# MCU.net
KiCad netlist of a schematic drawn in EAGLE
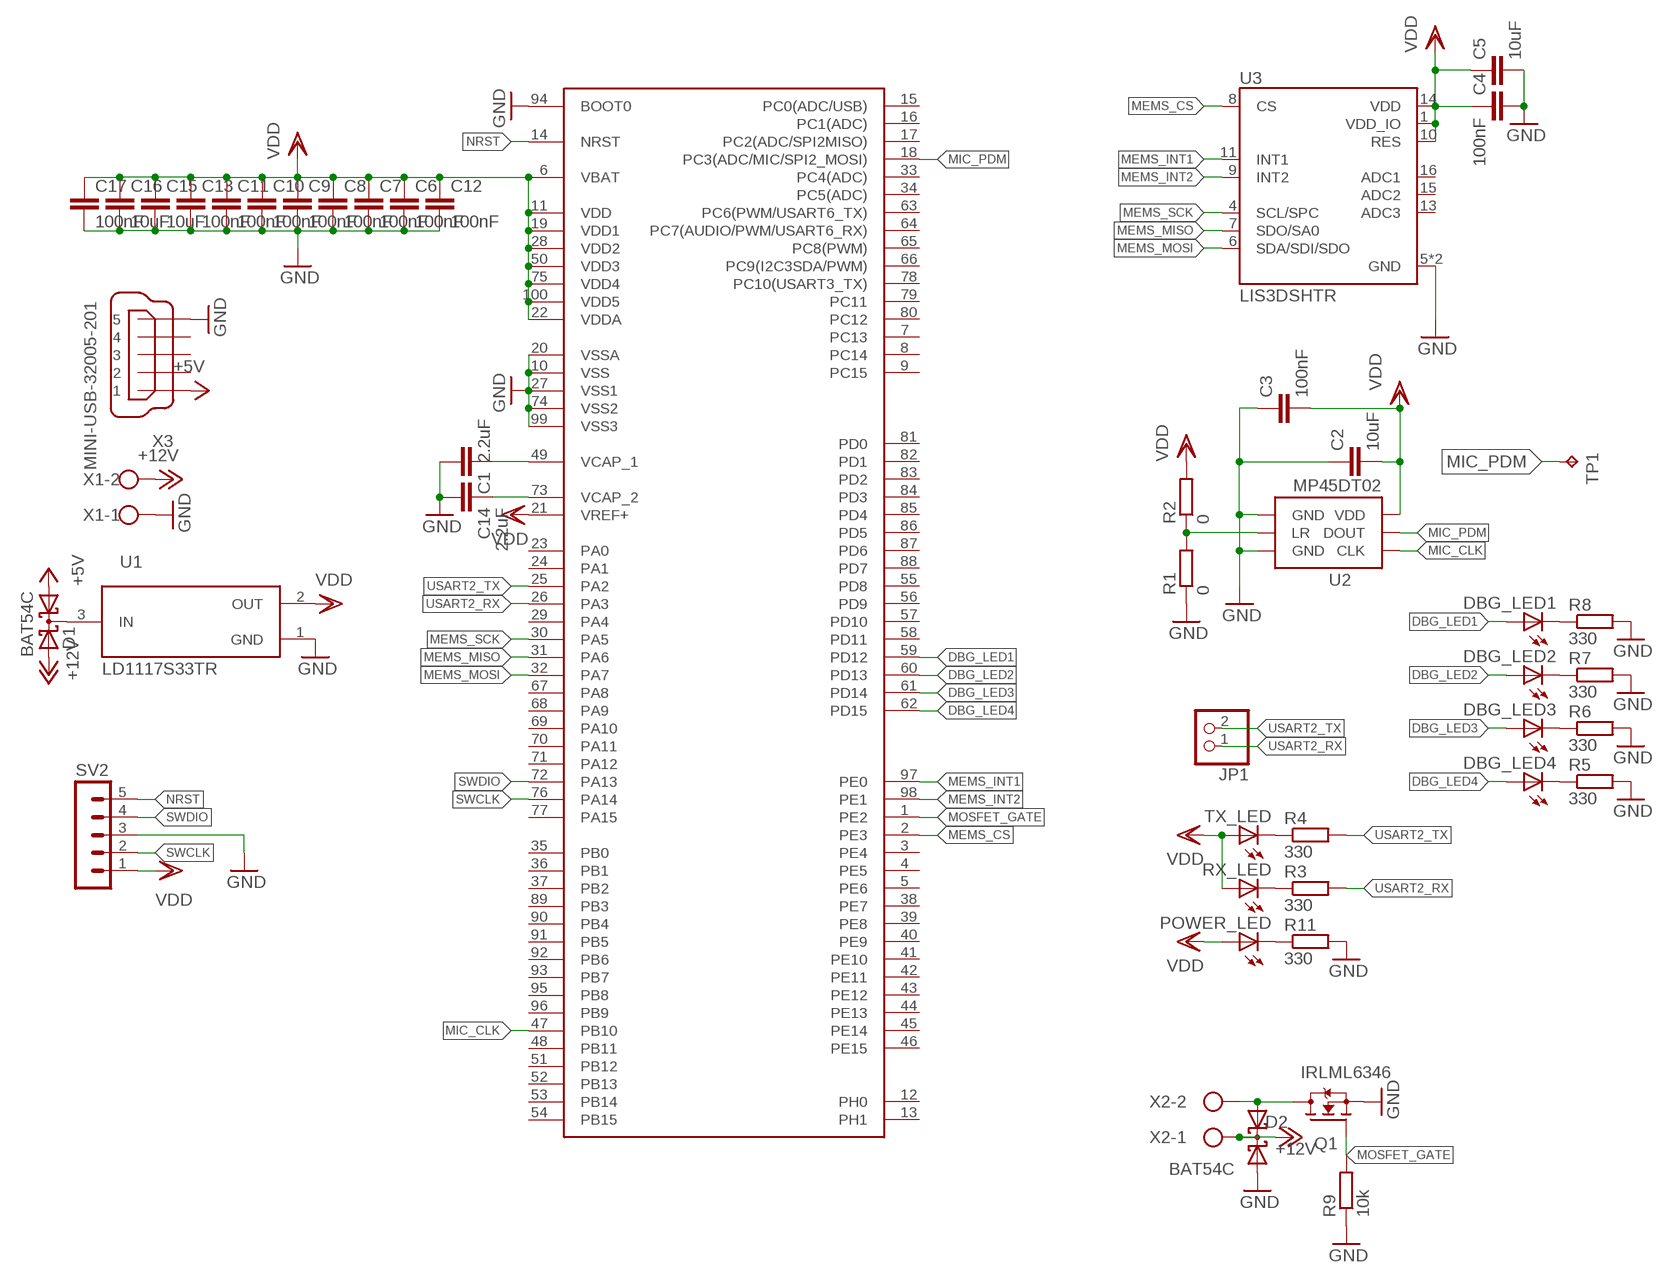
[diagram p0: schematic, sheet 1]

(export (version "E")
  (design (tool "Eeschema 10.0.6"))
  (components
    (comp (ref "C1")
      (value "2.2uF")
      (footprint "eagle-import:C0603")
      (libsource (lib "eagle-import") (part "C-EUC0603"))
    )
    (comp (ref "C2")
      (value "10uF")
      (footprint "eagle-import:C0805")
      (libsource (lib "eagle-import") (part "C-EUC0805"))
    )
    (comp (ref "C3")
      (value "100nF")
      (footprint "eagle-import:C0603")
      (libsource (lib "eagle-import") (part "C-EUC0603"))
    )
    (comp (ref "C4")
      (value "100nF")
      (footprint "eagle-import:C0603")
      (libsource (lib "eagle-import") (part "C-EUC0603"))
    )
    (comp (ref "C5")
      (value "10uF")
      (footprint "eagle-import:C0805")
      (libsource (lib "eagle-import") (part "C-EUC0805"))
    )
    (comp (ref "C6")
      (value "100nF")
      (footprint "eagle-import:C0603")
      (libsource (lib "eagle-import") (part "C-EUC0603"))
    )
    (comp (ref "C7")
      (value "100nF")
      (footprint "eagle-import:C0603")
      (libsource (lib "eagle-import") (part "C-EUC0603"))
    )
    (comp (ref "C8")
      (value "100nF")
      (footprint "eagle-import:C0603")
      (libsource (lib "eagle-import") (part "C-EUC0603"))
    )
    (comp (ref "C9")
      (value "100nF")
      (footprint "eagle-import:C0603")
      (libsource (lib "eagle-import") (part "C-EUC0603"))
    )
    (comp (ref "C10")
      (value "100nF")
      (footprint "eagle-import:C0603")
      (libsource (lib "eagle-import") (part "C-EUC0603"))
    )
    (comp (ref "C11")
      (value "100nF")
      (footprint "eagle-import:C0603")
      (libsource (lib "eagle-import") (part "C-EUC0603"))
    )
    (comp (ref "C12")
      (value "100nF")
      (footprint "eagle-import:C0603")
      (libsource (lib "eagle-import") (part "C-EUC0603"))
    )
    (comp (ref "C13")
      (value "100nF")
      (footprint "eagle-import:C0603")
      (libsource (lib "eagle-import") (part "C-EUC0603"))
    )
    (comp (ref "C14")
      (value "2.2uF")
      (footprint "eagle-import:C0603")
      (libsource (lib "eagle-import") (part "C-EUC0603"))
    )
    (comp (ref "C15")
      (value "10uF")
      (footprint "eagle-import:C0805")
      (libsource (lib "eagle-import") (part "C-EUC0805"))
    )
    (comp (ref "C16")
      (value "10uF")
      (footprint "eagle-import:C0805")
      (libsource (lib "eagle-import") (part "C-EUC0805"))
    )
    (comp (ref "C17")
      (value "100nF")
      (footprint "eagle-import:C0603")
      (libsource (lib "eagle-import") (part "C-EUC0603"))
    )
    (comp (ref "D1")
      (value "BAT54C")
      (footprint "eagle-import:SOT23")
      (libsource (lib "eagle-import") (part "BAT54C"))
    )
    (comp (ref "D2")
      (value "BAT54C")
      (footprint "eagle-import:SOT23")
      (libsource (lib "eagle-import") (part "BAT54C"))
    )
    (comp (ref "DBG_LED1")
      (value "LEDCHIP-LED0603")
      (footprint "eagle-import:CHIP-LED0603")
      (libsource (lib "eagle-import") (part "LEDCHIP-LED0603"))
    )
    (comp (ref "DBG_LED2")
      (value "LEDCHIP-LED0603")
      (footprint "eagle-import:CHIP-LED0603")
      (libsource (lib "eagle-import") (part "LEDCHIP-LED0603"))
    )
    (comp (ref "DBG_LED3")
      (value "LEDCHIP-LED0603")
      (footprint "eagle-import:CHIP-LED0603")
      (libsource (lib "eagle-import") (part "LEDCHIP-LED0603"))
    )
    (comp (ref "DBG_LED4")
      (value "LEDCHIP-LED0603")
      (footprint "eagle-import:CHIP-LED0603")
      (libsource (lib "eagle-import") (part "LEDCHIP-LED0603"))
    )
    (comp (ref "JP1")
      (value "PINHD-1X2")
      (footprint "eagle-import:1X02")
      (libsource (lib "eagle-import") (part "PINHD-1X2"))
    )
    (comp (ref "POWER_LED")
      (value "LEDCHIP-LED0603")
      (footprint "eagle-import:CHIP-LED0603")
      (libsource (lib "eagle-import") (part "LEDCHIP-LED0603"))
    )
    (comp (ref "Q1")
      (value "IRLML6346")
      (footprint "eagle-import:SOT23")
      (fields (field (name "MF") "Fairchild") (field (name "MPN") "BSS138"))
      (libsource (lib "eagle-import") (part "IRLML6346"))
    )
    (comp (ref "R1")
      (value "0")
      (footprint "eagle-import:R0603")
      (libsource (lib "eagle-import") (part "R-EU_R0603"))
    )
    (comp (ref "R2")
      (value "0")
      (footprint "eagle-import:R0603")
      (libsource (lib "eagle-import") (part "R-EU_R0603"))
    )
    (comp (ref "R3")
      (value "330")
      (footprint "eagle-import:R0603")
      (libsource (lib "eagle-import") (part "R-EU_R0603"))
    )
    (comp (ref "R4")
      (value "330")
      (footprint "eagle-import:R0603")
      (libsource (lib "eagle-import") (part "R-EU_R0603"))
    )
    (comp (ref "R5")
      (value "330")
      (footprint "eagle-import:R0603")
      (libsource (lib "eagle-import") (part "R-EU_R0603"))
    )
    (comp (ref "R6")
      (value "330")
      (footprint "eagle-import:R0603")
      (libsource (lib "eagle-import") (part "R-EU_R0603"))
    )
    (comp (ref "R7")
      (value "330")
      (footprint "eagle-import:R0603")
      (libsource (lib "eagle-import") (part "R-EU_R0603"))
    )
    (comp (ref "R8")
      (value "330")
      (footprint "eagle-import:R0603")
      (libsource (lib "eagle-import") (part "R-EU_R0603"))
    )
    (comp (ref "R9")
      (value "10k")
      (footprint "eagle-import:R0603")
      (libsource (lib "eagle-import") (part "R-EU_R0603"))
    )
    (comp (ref "R11")
      (value "330")
      (footprint "eagle-import:R0603")
      (libsource (lib "eagle-import") (part "R-EU_R0603"))
    )
    (comp (ref "RX_LED")
      (value "LEDCHIP-LED0603")
      (footprint "eagle-import:CHIP-LED0603")
      (libsource (lib "eagle-import") (part "LEDCHIP-LED0603"))
    )
    (comp (ref "SV2")
      (value "MA05-1")
      (footprint "eagle-import:MA05-1")
      (libsource (lib "eagle-import") (part "MA05-1"))
    )
    (comp (ref "TP1")
      (value "TPB1,27")
      (footprint "eagle-import:B1,27")
      (libsource (lib "eagle-import") (part "TPB1,27"))
    )
    (comp (ref "TX_LED")
      (value "LEDCHIP-LED0603")
      (footprint "eagle-import:CHIP-LED0603")
      (libsource (lib "eagle-import") (part "LEDCHIP-LED0603"))
    )
    (comp (ref "U$1")
      (value "STM32F407STM32D40X")
      (footprint "eagle-import:LQFP100")
      (libsource (lib "eagle-import") (part "STM32F407STM32D40X"))
    )
    (comp (ref "U1")
      (value "LD1117S33TR")
      (footprint "eagle-import:SOT230P700X180-4N")
      (fields (field (name "MF") "STMicroelectronics"))
      (libsource (lib "eagle-import") (part "LD1117S33TR"))
    )
    (comp (ref "U2")
      (value "MP45DT02")
      (footprint "eagle-import:ST_HLGA6")
      (fields (field (name "MF") "STMicroelectronics"))
      (libsource (lib "eagle-import") (part "MP45DT02"))
    )
    (comp (ref "U3")
      (value "LIS3DSHTR")
      (footprint "eagle-import:LGA16R50P5X3_300X300X100N")
      (fields (field (name "MF") "STMicroelectronics"))
      (libsource (lib "eagle-import") (part "LIS3DSHTR"))
    )
    (comp (ref "X1")
      (value "W237-102")
      (footprint "eagle-import:W237-102")
      (fields (field (name "MPN") "237-102"))
      (libsource (lib "eagle-import") (part "W237-102"))
    )
    (comp (ref "X2")
      (value "W237-102")
      (footprint "eagle-import:W237-102")
      (fields (field (name "MPN") "237-102"))
      (libsource (lib "eagle-import") (part "W237-102"))
    )
    (comp (ref "X3")
      (value "MINI-USB-32005-201")
      (footprint "eagle-import:32005-201")
      (libsource (lib "eagle-import") (part "MINI-USB-32005-201"))
    )
  )
  (nets
    (net (code "1") (name "+5V") (class "Default")
      (node (ref "D1") (pin "1") (pinfunction "A1_1") (pintype "passive"))
      (node (ref "X3") (pin "1") (pinfunction "1_1") (pintype "passive"))
    )
    (net (code "2") (name "+12V") (class "Default")
      (node (ref "D1") (pin "2") (pinfunction "A2_2") (pintype "passive"))
      (node (ref "D2") (pin "3") (pinfunction "CC_3") (pintype "passive"))
      (node (ref "X1") (pin "2") (pinfunction "KL_2") (pintype "passive"))
      (node (ref "X2") (pin "1") (pinfunction "KL_1") (pintype "passive"))
    )
    (net (code "3") (name "DBG_LED1") (class "Default")
      (node (ref "DBG_LED1") (pin "A") (pinfunction "A_A") (pintype "passive"))
      (node (ref "U$1") (pin "59") (pinfunction "PD12_59") (pintype "bidirectional"))
    )
    (net (code "4") (name "DBG_LED2") (class "Default")
      (node (ref "DBG_LED2") (pin "A") (pinfunction "A_A") (pintype "passive"))
      (node (ref "U$1") (pin "60") (pinfunction "PD13_60") (pintype "bidirectional"))
    )
    (net (code "5") (name "DBG_LED3") (class "Default")
      (node (ref "DBG_LED3") (pin "A") (pinfunction "A_A") (pintype "passive"))
      (node (ref "U$1") (pin "61") (pinfunction "PD14_61") (pintype "bidirectional"))
    )
    (net (code "6") (name "DBG_LED4") (class "Default")
      (node (ref "DBG_LED4") (pin "A") (pinfunction "A_A") (pintype "passive"))
      (node (ref "U$1") (pin "62") (pinfunction "PD15_62") (pintype "bidirectional"))
    )
    (net (code "7") (name "GND") (class "Default")
      (node (ref "C1") (pin "2") (pinfunction "2_2") (pintype "passive"))
      (node (ref "C10") (pin "2") (pinfunction "2_2") (pintype "passive"))
      (node (ref "C11") (pin "2") (pinfunction "2_2") (pintype "passive"))
      (node (ref "C12") (pin "2") (pinfunction "2_2") (pintype "passive"))
      (node (ref "C13") (pin "2") (pinfunction "2_2") (pintype "passive"))
      (node (ref "C14") (pin "2") (pinfunction "2_2") (pintype "passive"))
      (node (ref "C15") (pin "2") (pinfunction "2_2") (pintype "passive"))
      (node (ref "C16") (pin "2") (pinfunction "2_2") (pintype "passive"))
      (node (ref "C17") (pin "2") (pinfunction "2_2") (pintype "passive"))
      (node (ref "C2") (pin "1") (pinfunction "1_1") (pintype "passive"))
      (node (ref "C3") (pin "1") (pinfunction "1_1") (pintype "passive"))
      (node (ref "C4") (pin "2") (pinfunction "2_2") (pintype "passive"))
      (node (ref "C5") (pin "2") (pinfunction "2_2") (pintype "passive"))
      (node (ref "C6") (pin "2") (pinfunction "2_2") (pintype "passive"))
      (node (ref "C7") (pin "2") (pinfunction "2_2") (pintype "passive"))
      (node (ref "C8") (pin "2") (pinfunction "2_2") (pintype "passive"))
      (node (ref "C9") (pin "2") (pinfunction "2_2") (pintype "passive"))
      (node (ref "D2") (pin "1") (pinfunction "A1_1") (pintype "passive"))
      (node (ref "Q1") (pin "2") (pinfunction "S_2") (pintype "passive"))
      (node (ref "R1") (pin "1") (pinfunction "1_1") (pintype "passive"))
      (node (ref "R11") (pin "2") (pinfunction "2_2") (pintype "passive"))
      (node (ref "R5") (pin "2") (pinfunction "2_2") (pintype "passive"))
      (node (ref "R6") (pin "2") (pinfunction "2_2") (pintype "passive"))
      (node (ref "R7") (pin "2") (pinfunction "2_2") (pintype "passive"))
      (node (ref "R8") (pin "2") (pinfunction "2_2") (pintype "passive"))
      (node (ref "R9") (pin "1") (pinfunction "1_1") (pintype "passive"))
      (node (ref "SV2") (pin "3") (pinfunction "3_3") (pintype "passive"))
      (node (ref "U$1") (pin "10") (pinfunction "VSS_10") (pintype "bidirectional"))
      (node (ref "U$1") (pin "20") (pinfunction "VSSA_20") (pintype "bidirectional"))
      (node (ref "U$1") (pin "27") (pinfunction "VSS1_27") (pintype "bidirectional"))
      (node (ref "U$1") (pin "74") (pinfunction "VSS2_74") (pintype "bidirectional"))
      (node (ref "U$1") (pin "94") (pinfunction "BOOT0_94") (pintype "bidirectional"))
      (node (ref "U$1") (pin "99") (pinfunction "VSS3_99") (pintype "bidirectional"))
      (node (ref "U1") (pin "1") (pinfunction "GND_1") (pintype "power_in"))
      (node (ref "U2") (pin "1") (pinfunction "GND_1") (pintype "bidirectional"))
      (node (ref "U2") (pin "3") (pinfunction "GND_3") (pintype "bidirectional"))
      (node (ref "U3") (pin "12") (pinfunction "GND_12") (pintype "power_in"))
      (node (ref "U3") (pin "5") (pinfunction "GND_5") (pintype "power_in"))
      (node (ref "X1") (pin "1") (pinfunction "KL_1") (pintype "passive"))
      (node (ref "X3") (pin "5") (pinfunction "5_5") (pintype "passive"))
    )
    (net (code "8") (name "MEMS_CS") (class "Default")
      (node (ref "U$1") (pin "2") (pinfunction "PE3_2") (pintype "bidirectional"))
      (node (ref "U3") (pin "8") (pinfunction "CS_8") (pintype "input"))
    )
    (net (code "9") (name "MEMS_INT1") (class "Default")
      (node (ref "U$1") (pin "97") (pinfunction "PE0_97") (pintype "bidirectional"))
      (node (ref "U3") (pin "11") (pinfunction "INT1_11") (pintype "input"))
    )
    (net (code "10") (name "MEMS_INT2") (class "Default")
      (node (ref "U$1") (pin "98") (pinfunction "PE1_98") (pintype "bidirectional"))
      (node (ref "U3") (pin "9") (pinfunction "INT2_9") (pintype "input"))
    )
    (net (code "11") (name "MEMS_MISO") (class "Default")
      (node (ref "U$1") (pin "31") (pinfunction "PA6_31") (pintype "bidirectional"))
      (node (ref "U3") (pin "7") (pinfunction "SDO/SA0_7") (pintype "output"))
    )
    (net (code "12") (name "MEMS_MOSI") (class "Default")
      (node (ref "U$1") (pin "32") (pinfunction "PA7_32") (pintype "bidirectional"))
      (node (ref "U3") (pin "6") (pinfunction "SDA/SDI/SDO_6") (pintype "bidirectional"))
    )
    (net (code "13") (name "MEMS_SCK") (class "Default")
      (node (ref "U$1") (pin "30") (pinfunction "PA5_30") (pintype "bidirectional"))
      (node (ref "U3") (pin "4") (pinfunction "SCL/SPC_4") (pintype "input"))
    )
    (net (code "14") (name "MIC_CLK") (class "Default")
      (node (ref "U$1") (pin "47") (pinfunction "PB10_47") (pintype "bidirectional"))
      (node (ref "U2") (pin "4") (pinfunction "CLK_4") (pintype "bidirectional"))
    )
    (net (code "15") (name "MIC_PDM") (class "Default")
      (node (ref "TP1") (pin "TP") (pinfunction "TP_TP") (pintype "input"))
      (node (ref "U$1") (pin "18") (pinfunction "PC3(ADC/MIC/SPI2_MOSI)_18") (pintype "bidirectional"))
      (node (ref "U2") (pin "5") (pinfunction "DOUT_5") (pintype "bidirectional"))
    )
    (net (code "16") (name "MOSFET_GATE") (class "Default")
      (node (ref "Q1") (pin "1") (pinfunction "G_1") (pintype "passive"))
      (node (ref "R9") (pin "2") (pinfunction "2_2") (pintype "passive"))
      (node (ref "U$1") (pin "1") (pinfunction "PE2_1") (pintype "bidirectional"))
    )
    (net (code "17") (name "NRST") (class "Default")
      (node (ref "SV2") (pin "5") (pinfunction "5_5") (pintype "passive"))
      (node (ref "U$1") (pin "14") (pinfunction "NRST_14") (pintype "bidirectional"))
    )
    (net (code "18") (name "Net-(D1-CC)") (class "Default")
      (node (ref "D1") (pin "3") (pinfunction "CC_3") (pintype "passive"))
      (node (ref "U1") (pin "3") (pinfunction "IN_3") (pintype "input"))
    )
    (net (code "19") (name "Net-(D2-A2)") (class "Default")
      (node (ref "D2") (pin "2") (pinfunction "A2_2") (pintype "passive"))
      (node (ref "Q1") (pin "3") (pinfunction "D_3") (pintype "passive"))
      (node (ref "X2") (pin "2") (pinfunction "KL_2") (pintype "passive"))
    )
    (net (code "20") (name "Net-(DBG_LED1-PadC)") (class "Default")
      (node (ref "DBG_LED1") (pin "C") (pinfunction "C_C") (pintype "passive"))
      (node (ref "R8") (pin "1") (pinfunction "1_1") (pintype "passive"))
    )
    (net (code "21") (name "Net-(DBG_LED2-PadC)") (class "Default")
      (node (ref "DBG_LED2") (pin "C") (pinfunction "C_C") (pintype "passive"))
      (node (ref "R7") (pin "1") (pinfunction "1_1") (pintype "passive"))
    )
    (net (code "22") (name "Net-(DBG_LED3-PadC)") (class "Default")
      (node (ref "DBG_LED3") (pin "C") (pinfunction "C_C") (pintype "passive"))
      (node (ref "R6") (pin "1") (pinfunction "1_1") (pintype "passive"))
    )
    (net (code "23") (name "Net-(DBG_LED4-PadC)") (class "Default")
      (node (ref "DBG_LED4") (pin "C") (pinfunction "C_C") (pintype "passive"))
      (node (ref "R5") (pin "1") (pinfunction "1_1") (pintype "passive"))
    )
    (net (code "24") (name "Net-(POWER_LED-PadC)") (class "Default")
      (node (ref "POWER_LED") (pin "C") (pinfunction "C_C") (pintype "passive"))
      (node (ref "R11") (pin "1") (pinfunction "1_1") (pintype "passive"))
    )
    (net (code "25") (name "Net-(R3-Pad1)") (class "Default")
      (node (ref "R3") (pin "1") (pinfunction "1_1") (pintype "passive"))
      (node (ref "RX_LED") (pin "C") (pinfunction "C_C") (pintype "passive"))
    )
    (net (code "26") (name "Net-(R4-Pad1)") (class "Default")
      (node (ref "R4") (pin "1") (pinfunction "1_1") (pintype "passive"))
      (node (ref "TX_LED") (pin "C") (pinfunction "C_C") (pintype "passive"))
    )
    (net (code "27") (name "Net-(U$1-VCAP_1)") (class "Default")
      (node (ref "C1") (pin "1") (pinfunction "1_1") (pintype "passive"))
      (node (ref "U$1") (pin "49") (pinfunction "VCAP_1_49") (pintype "bidirectional"))
    )
    (net (code "28") (name "Net-(U$1-VCAP_2)") (class "Default")
      (node (ref "C14") (pin "1") (pinfunction "1_1") (pintype "passive"))
      (node (ref "U$1") (pin "73") (pinfunction "VCAP_2_73") (pintype "bidirectional"))
    )
    (net (code "29") (name "Net-(U2-LR)") (class "Default")
      (node (ref "R1") (pin "2") (pinfunction "2_2") (pintype "passive"))
      (node (ref "R2") (pin "1") (pinfunction "1_1") (pintype "passive"))
      (node (ref "U2") (pin "2") (pinfunction "LR_2") (pintype "bidirectional"))
    )
    (net (code "30") (name "SWCLK") (class "Default")
      (node (ref "SV2") (pin "2") (pinfunction "2_2") (pintype "passive"))
      (node (ref "U$1") (pin "76") (pinfunction "PA14_76") (pintype "bidirectional"))
    )
    (net (code "31") (name "SWDIO") (class "Default")
      (node (ref "SV2") (pin "4") (pinfunction "4_4") (pintype "passive"))
      (node (ref "U$1") (pin "72") (pinfunction "PA13_72") (pintype "bidirectional"))
    )
    (net (code "32") (name "USART2_RX") (class "Default")
      (node (ref "JP1") (pin "1") (pinfunction "1_1") (pintype "passive"))
      (node (ref "R3") (pin "2") (pinfunction "2_2") (pintype "passive"))
      (node (ref "U$1") (pin "26") (pinfunction "PA3_26") (pintype "bidirectional"))
    )
    (net (code "33") (name "USART2_TX") (class "Default")
      (node (ref "JP1") (pin "2") (pinfunction "2_2") (pintype "passive"))
      (node (ref "R4") (pin "2") (pinfunction "2_2") (pintype "passive"))
      (node (ref "U$1") (pin "25") (pinfunction "PA2_25") (pintype "bidirectional"))
    )
    (net (code "34") (name "VDD") (class "Default")
      (node (ref "C10") (pin "1") (pinfunction "1_1") (pintype "passive"))
      (node (ref "C11") (pin "1") (pinfunction "1_1") (pintype "passive"))
      (node (ref "C12") (pin "1") (pinfunction "1_1") (pintype "passive"))
      (node (ref "C13") (pin "1") (pinfunction "1_1") (pintype "passive"))
      (node (ref "C15") (pin "1") (pinfunction "1_1") (pintype "passive"))
      (node (ref "C16") (pin "1") (pinfunction "1_1") (pintype "passive"))
      (node (ref "C17") (pin "1") (pinfunction "1_1") (pintype "passive"))
      (node (ref "C2") (pin "2") (pinfunction "2_2") (pintype "passive"))
      (node (ref "C3") (pin "2") (pinfunction "2_2") (pintype "passive"))
      (node (ref "C4") (pin "1") (pinfunction "1_1") (pintype "passive"))
      (node (ref "C5") (pin "1") (pinfunction "1_1") (pintype "passive"))
      (node (ref "C6") (pin "1") (pinfunction "1_1") (pintype "passive"))
      (node (ref "C7") (pin "1") (pinfunction "1_1") (pintype "passive"))
      (node (ref "C8") (pin "1") (pinfunction "1_1") (pintype "passive"))
      (node (ref "C9") (pin "1") (pinfunction "1_1") (pintype "passive"))
      (node (ref "POWER_LED") (pin "A") (pinfunction "A_A") (pintype "passive"))
      (node (ref "R2") (pin "2") (pinfunction "2_2") (pintype "passive"))
      (node (ref "RX_LED") (pin "A") (pinfunction "A_A") (pintype "passive"))
      (node (ref "SV2") (pin "1") (pinfunction "1_1") (pintype "passive"))
      (node (ref "TX_LED") (pin "A") (pinfunction "A_A") (pintype "passive"))
      (node (ref "U$1") (pin "100") (pinfunction "VDD5_100") (pintype "bidirectional"))
      (node (ref "U$1") (pin "11") (pinfunction "VDD_11") (pintype "bidirectional"))
      (node (ref "U$1") (pin "19") (pinfunction "VDD1_19") (pintype "bidirectional"))
      (node (ref "U$1") (pin "21") (pinfunction "VREF+_21") (pintype "bidirectional"))
      (node (ref "U$1") (pin "22") (pinfunction "VDDA_22") (pintype "bidirectional"))
      (node (ref "U$1") (pin "28") (pinfunction "VDD2_28") (pintype "bidirectional"))
      (node (ref "U$1") (pin "50") (pinfunction "VDD3_50") (pintype "bidirectional"))
      (node (ref "U$1") (pin "6") (pinfunction "VBAT_6") (pintype "bidirectional"))
      (node (ref "U$1") (pin "75") (pinfunction "VDD4_75") (pintype "bidirectional"))
      (node (ref "U1") (pin "2") (pinfunction "OUT_2") (pintype "output"))
      (node (ref "U2") (pin "6") (pinfunction "VDD_6") (pintype "bidirectional"))
      (node (ref "U3") (pin "1") (pinfunction "VDD_IO_1") (pintype "power_in"))
      (node (ref "U3") (pin "10") (pinfunction "RES_10") (pintype "power_in"))
      (node (ref "U3") (pin "14") (pinfunction "VDD_14") (pintype "power_in"))
    )
    (net (code "35") (name "unconnected-(U$1-PA0-Pad23)") (class "Default")
      (node (ref "U$1") (pin "23") (pinfunction "PA0_23") (pintype "bidirectional"))
    )
    (net (code "36") (name "unconnected-(U$1-PA1-Pad24)") (class "Default")
      (node (ref "U$1") (pin "24") (pinfunction "PA1_24") (pintype "bidirectional"))
    )
    (net (code "37") (name "unconnected-(U$1-PA4-Pad29)") (class "Default")
      (node (ref "U$1") (pin "29") (pinfunction "PA4_29") (pintype "bidirectional"))
    )
    (net (code "38") (name "unconnected-(U$1-PA8-Pad67)") (class "Default")
      (node (ref "U$1") (pin "67") (pinfunction "PA8_67") (pintype "bidirectional"))
    )
    (net (code "39") (name "unconnected-(U$1-PA9-Pad68)") (class "Default")
      (node (ref "U$1") (pin "68") (pinfunction "PA9_68") (pintype "bidirectional"))
    )
    (net (code "40") (name "unconnected-(U$1-PA10-Pad69)") (class "Default")
      (node (ref "U$1") (pin "69") (pinfunction "PA10_69") (pintype "bidirectional"))
    )
    (net (code "41") (name "unconnected-(U$1-PA11-Pad70)") (class "Default")
      (node (ref "U$1") (pin "70") (pinfunction "PA11_70") (pintype "bidirectional"))
    )
    (net (code "42") (name "unconnected-(U$1-PA12-Pad71)") (class "Default")
      (node (ref "U$1") (pin "71") (pinfunction "PA12_71") (pintype "bidirectional"))
    )
    (net (code "43") (name "unconnected-(U$1-PA15-Pad77)") (class "Default")
      (node (ref "U$1") (pin "77") (pinfunction "PA15_77") (pintype "bidirectional"))
    )
    (net (code "44") (name "unconnected-(U$1-PB0-Pad35)") (class "Default")
      (node (ref "U$1") (pin "35") (pinfunction "PB0_35") (pintype "bidirectional"))
    )
    (net (code "45") (name "unconnected-(U$1-PB1-Pad36)") (class "Default")
      (node (ref "U$1") (pin "36") (pinfunction "PB1_36") (pintype "bidirectional"))
    )
    (net (code "46") (name "unconnected-(U$1-PB2-Pad37)") (class "Default")
      (node (ref "U$1") (pin "37") (pinfunction "PB2_37") (pintype "bidirectional"))
    )
    (net (code "47") (name "unconnected-(U$1-PB3-Pad89)") (class "Default")
      (node (ref "U$1") (pin "89") (pinfunction "PB3_89") (pintype "bidirectional"))
    )
    (net (code "48") (name "unconnected-(U$1-PB4-Pad90)") (class "Default")
      (node (ref "U$1") (pin "90") (pinfunction "PB4_90") (pintype "bidirectional"))
    )
    (net (code "49") (name "unconnected-(U$1-PB5-Pad91)") (class "Default")
      (node (ref "U$1") (pin "91") (pinfunction "PB5_91") (pintype "bidirectional"))
    )
    (net (code "50") (name "unconnected-(U$1-PB6-Pad92)") (class "Default")
      (node (ref "U$1") (pin "92") (pinfunction "PB6_92") (pintype "bidirectional"))
    )
    (net (code "51") (name "unconnected-(U$1-PB7-Pad93)") (class "Default")
      (node (ref "U$1") (pin "93") (pinfunction "PB7_93") (pintype "bidirectional"))
    )
    (net (code "52") (name "unconnected-(U$1-PB8-Pad95)") (class "Default")
      (node (ref "U$1") (pin "95") (pinfunction "PB8_95") (pintype "bidirectional"))
    )
    (net (code "53") (name "unconnected-(U$1-PB9-Pad96)") (class "Default")
      (node (ref "U$1") (pin "96") (pinfunction "PB9_96") (pintype "bidirectional"))
    )
    (net (code "54") (name "unconnected-(U$1-PB11-Pad48)") (class "Default")
      (node (ref "U$1") (pin "48") (pinfunction "PB11_48") (pintype "bidirectional"))
    )
    (net (code "55") (name "unconnected-(U$1-PB12-Pad51)") (class "Default")
      (node (ref "U$1") (pin "51") (pinfunction "PB12_51") (pintype "bidirectional"))
    )
    (net (code "56") (name "unconnected-(U$1-PB13-Pad52)") (class "Default")
      (node (ref "U$1") (pin "52") (pinfunction "PB13_52") (pintype "bidirectional"))
    )
    (net (code "57") (name "unconnected-(U$1-PB14-Pad53)") (class "Default")
      (node (ref "U$1") (pin "53") (pinfunction "PB14_53") (pintype "bidirectional"))
    )
    (net (code "58") (name "unconnected-(U$1-PB15-Pad54)") (class "Default")
      (node (ref "U$1") (pin "54") (pinfunction "PB15_54") (pintype "bidirectional"))
    )
    (net (code "59") (name "unconnected-(U$1-PC0(ADC{slash}USB)-Pad15)") (class "Default")
      (node (ref "U$1") (pin "15") (pinfunction "PC0(ADC/USB)_15") (pintype "bidirectional"))
    )
    (net (code "60") (name "unconnected-(U$1-PC1(ADC)-Pad16)") (class "Default")
      (node (ref "U$1") (pin "16") (pinfunction "PC1(ADC)_16") (pintype "bidirectional"))
    )
    (net (code "61") (name "unconnected-(U$1-PC2(ADC{slash}SPI2MISO)-Pad17)") (class "Default")
      (node (ref "U$1") (pin "17") (pinfunction "PC2(ADC/SPI2MISO)_17") (pintype "bidirectional"))
    )
    (net (code "62") (name "unconnected-(U$1-PC4(ADC)-Pad33)") (class "Default")
      (node (ref "U$1") (pin "33") (pinfunction "PC4(ADC)_33") (pintype "bidirectional"))
    )
    (net (code "63") (name "unconnected-(U$1-PC5(ADC)-Pad34)") (class "Default")
      (node (ref "U$1") (pin "34") (pinfunction "PC5(ADC)_34") (pintype "bidirectional"))
    )
    (net (code "64") (name "unconnected-(U$1-PC6(PWM{slash}USART6_TX)-Pad63)") (class "Default")
      (node (ref "U$1") (pin "63") (pinfunction "PC6(PWM/USART6_TX)_63") (pintype "bidirectional"))
    )
    (net (code "65") (name "unconnected-(U$1-PC7(AUDIO{slash}PWM{slash}USART6_RX)-Pad64)") (class "Default")
      (node (ref "U$1") (pin "64") (pinfunction "PC7(AUDIO/PWM/USART6_RX)_64") (pintype "bidirectional"))
    )
    (net (code "66") (name "unconnected-(U$1-PC8(PWM)-Pad65)") (class "Default")
      (node (ref "U$1") (pin "65") (pinfunction "PC8(PWM)_65") (pintype "bidirectional"))
    )
    (net (code "67") (name "unconnected-(U$1-PC9(I2C3SDA{slash}PWM)-Pad66)") (class "Default")
      (node (ref "U$1") (pin "66") (pinfunction "PC9(I2C3SDA/PWM)_66") (pintype "bidirectional"))
    )
    (net (code "68") (name "unconnected-(U$1-PC10(USART3_TX)-Pad78)") (class "Default")
      (node (ref "U$1") (pin "78") (pinfunction "PC10(USART3_TX)_78") (pintype "bidirectional"))
    )
    (net (code "69") (name "unconnected-(U$1-PC11-Pad79)") (class "Default")
      (node (ref "U$1") (pin "79") (pinfunction "PC11_79") (pintype "bidirectional"))
    )
    (net (code "70") (name "unconnected-(U$1-PC12-Pad80)") (class "Default")
      (node (ref "U$1") (pin "80") (pinfunction "PC12_80") (pintype "bidirectional"))
    )
    (net (code "71") (name "unconnected-(U$1-PC13-Pad7)") (class "Default")
      (node (ref "U$1") (pin "7") (pinfunction "PC13_7") (pintype "bidirectional"))
    )
    (net (code "72") (name "unconnected-(U$1-PC14-Pad8)") (class "Default")
      (node (ref "U$1") (pin "8") (pinfunction "PC14_8") (pintype "bidirectional"))
    )
    (net (code "73") (name "unconnected-(U$1-PC15-Pad9)") (class "Default")
      (node (ref "U$1") (pin "9") (pinfunction "PC15_9") (pintype "bidirectional"))
    )
    (net (code "74") (name "unconnected-(U$1-PD0-Pad81)") (class "Default")
      (node (ref "U$1") (pin "81") (pinfunction "PD0_81") (pintype "bidirectional"))
    )
    (net (code "75") (name "unconnected-(U$1-PD1-Pad82)") (class "Default")
      (node (ref "U$1") (pin "82") (pinfunction "PD1_82") (pintype "bidirectional"))
    )
    (net (code "76") (name "unconnected-(U$1-PD2-Pad83)") (class "Default")
      (node (ref "U$1") (pin "83") (pinfunction "PD2_83") (pintype "bidirectional"))
    )
    (net (code "77") (name "unconnected-(U$1-PD3-Pad84)") (class "Default")
      (node (ref "U$1") (pin "84") (pinfunction "PD3_84") (pintype "bidirectional"))
    )
    (net (code "78") (name "unconnected-(U$1-PD4-Pad85)") (class "Default")
      (node (ref "U$1") (pin "85") (pinfunction "PD4_85") (pintype "bidirectional"))
    )
    (net (code "79") (name "unconnected-(U$1-PD5-Pad86)") (class "Default")
      (node (ref "U$1") (pin "86") (pinfunction "PD5_86") (pintype "bidirectional"))
    )
    (net (code "80") (name "unconnected-(U$1-PD6-Pad87)") (class "Default")
      (node (ref "U$1") (pin "87") (pinfunction "PD6_87") (pintype "bidirectional"))
    )
    (net (code "81") (name "unconnected-(U$1-PD7-Pad88)") (class "Default")
      (node (ref "U$1") (pin "88") (pinfunction "PD7_88") (pintype "bidirectional"))
    )
    (net (code "82") (name "unconnected-(U$1-PD8-Pad55)") (class "Default")
      (node (ref "U$1") (pin "55") (pinfunction "PD8_55") (pintype "bidirectional"))
    )
    (net (code "83") (name "unconnected-(U$1-PD9-Pad56)") (class "Default")
      (node (ref "U$1") (pin "56") (pinfunction "PD9_56") (pintype "bidirectional"))
    )
    (net (code "84") (name "unconnected-(U$1-PD10-Pad57)") (class "Default")
      (node (ref "U$1") (pin "57") (pinfunction "PD10_57") (pintype "bidirectional"))
    )
    (net (code "85") (name "unconnected-(U$1-PD11-Pad58)") (class "Default")
      (node (ref "U$1") (pin "58") (pinfunction "PD11_58") (pintype "bidirectional"))
    )
    (net (code "86") (name "unconnected-(U$1-PE4-Pad3)") (class "Default")
      (node (ref "U$1") (pin "3") (pinfunction "PE4_3") (pintype "bidirectional"))
    )
    (net (code "87") (name "unconnected-(U$1-PE5-Pad4)") (class "Default")
      (node (ref "U$1") (pin "4") (pinfunction "PE5_4") (pintype "bidirectional"))
    )
    (net (code "88") (name "unconnected-(U$1-PE6-Pad5)") (class "Default")
      (node (ref "U$1") (pin "5") (pinfunction "PE6_5") (pintype "bidirectional"))
    )
    (net (code "89") (name "unconnected-(U$1-PE7-Pad38)") (class "Default")
      (node (ref "U$1") (pin "38") (pinfunction "PE7_38") (pintype "bidirectional"))
    )
    (net (code "90") (name "unconnected-(U$1-PE8-Pad39)") (class "Default")
      (node (ref "U$1") (pin "39") (pinfunction "PE8_39") (pintype "bidirectional"))
    )
    (net (code "91") (name "unconnected-(U$1-PE9-Pad40)") (class "Default")
      (node (ref "U$1") (pin "40") (pinfunction "PE9_40") (pintype "bidirectional"))
    )
    (net (code "92") (name "unconnected-(U$1-PE10-Pad41)") (class "Default")
      (node (ref "U$1") (pin "41") (pinfunction "PE10_41") (pintype "bidirectional"))
    )
    (net (code "93") (name "unconnected-(U$1-PE11-Pad42)") (class "Default")
      (node (ref "U$1") (pin "42") (pinfunction "PE11_42") (pintype "bidirectional"))
    )
    (net (code "94") (name "unconnected-(U$1-PE12-Pad43)") (class "Default")
      (node (ref "U$1") (pin "43") (pinfunction "PE12_43") (pintype "bidirectional"))
    )
    (net (code "95") (name "unconnected-(U$1-PE13-Pad44)") (class "Default")
      (node (ref "U$1") (pin "44") (pinfunction "PE13_44") (pintype "bidirectional"))
    )
    (net (code "96") (name "unconnected-(U$1-PE14-Pad45)") (class "Default")
      (node (ref "U$1") (pin "45") (pinfunction "PE14_45") (pintype "bidirectional"))
    )
    (net (code "97") (name "unconnected-(U$1-PE15-Pad46)") (class "Default")
      (node (ref "U$1") (pin "46") (pinfunction "PE15_46") (pintype "bidirectional"))
    )
    (net (code "98") (name "unconnected-(U$1-PH0-Pad12)") (class "Default")
      (node (ref "U$1") (pin "12") (pinfunction "PH0_12") (pintype "bidirectional"))
    )
    (net (code "99") (name "unconnected-(U$1-PH1-Pad13)") (class "Default")
      (node (ref "U$1") (pin "13") (pinfunction "PH1_13") (pintype "bidirectional"))
    )
    (net (code "100") (name "unconnected-(U3-ADC1-Pad16)") (class "Default")
      (node (ref "U3") (pin "16") (pinfunction "ADC1_16") (pintype "input"))
    )
    (net (code "101") (name "unconnected-(U3-ADC2-Pad15)") (class "Default")
      (node (ref "U3") (pin "15") (pinfunction "ADC2_15") (pintype "input"))
    )
    (net (code "102") (name "unconnected-(U3-ADC3-Pad13)") (class "Default")
      (node (ref "U3") (pin "13") (pinfunction "ADC3_13") (pintype "input"))
    )
    (net (code "103") (name "unconnected-(X3-Pad2)") (class "Default")
      (node (ref "X3") (pin "2") (pinfunction "2_2") (pintype "passive"))
    )
    (net (code "104") (name "unconnected-(X3-Pad3)") (class "Default")
      (node (ref "X3") (pin "3") (pinfunction "3_3") (pintype "passive"))
    )
    (net (code "105") (name "unconnected-(X3-Pad4)") (class "Default")
      (node (ref "X3") (pin "4") (pinfunction "4_4") (pintype "passive"))
    )
  )
)
